# Power.net
KiCad netlist of a schematic drawn in Altium Designer
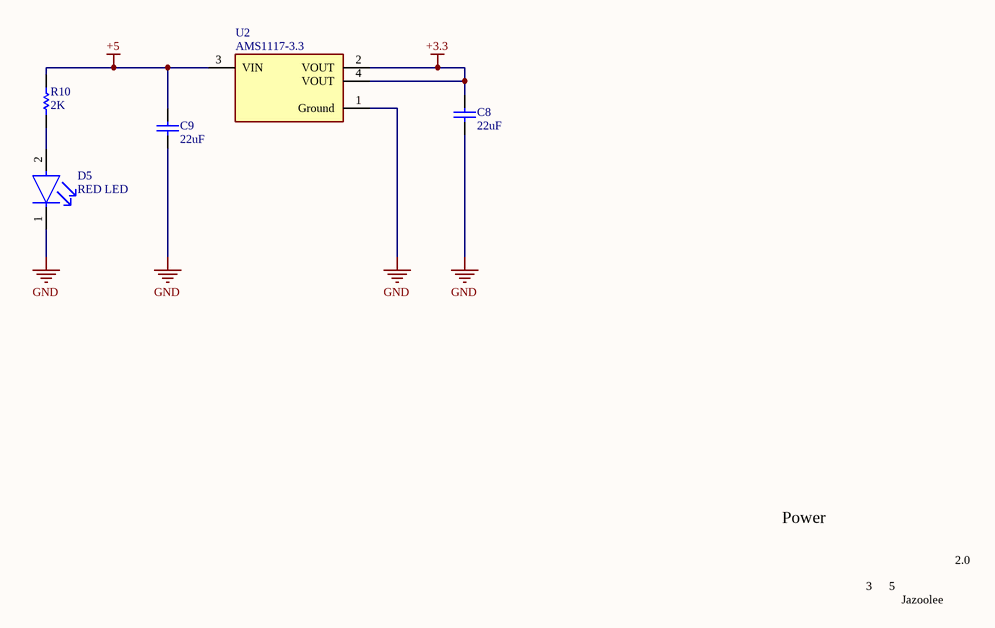
[diagram p0: Power.SchDoc]

(export (version "E")
  (design (tool "Eeschema 10.0.6"))
  (components
    (comp (ref "C8")
      (value "22uF")
      (footprint "CAPC2014X150X70ML20")
      (description "22uF 10V 20% Tantalum 0805")
      (fields
        (field (name "PART NUMBER") "TACR226M010XTA")
        (field (name "MANUFACTURER") "AVX Interconnect / Elco")
      )
      (libsource (lib "Altium Content Vault") (part "CAP"))
    )
    (comp (ref "C9")
      (value "22uF")
      (footprint "CAPC2014X150X70ML20")
      (description "22uF 10V 20% Tantalum 0805")
      (fields
        (field (name "PART NUMBER") "TACR226M010XTA")
        (field (name "MANUFACTURER") "AVX Interconnect / Elco")
      )
      (libsource (lib "Altium Content Vault") (part "CAP"))
    )
    (comp (ref "D5")
      (value "HSMS-C150")
      (footprint "FP-HSMS-C150-MFG")
      (description "LED RED")
      (fields (field (name "COLOR") "RED LED"))
      (libsource (lib "Altium Content Vault") (part "8706943c75ba83719d021d2fdc84c58"))
    )
    (comp (ref "R10")
      (value "2K")
      (footprint "RESC2013X60X35LL10T20")
      (fields (field (name "PART NUMBER") "RT0805FRE072KL") (field (name "MANUFACTURER") "Yageo"))
      (libsource (lib "Altium Content Vault") (part "RES"))
    )
    (comp (ref "U2")
      (value "AMS1117-3.3")
      (footprint "FP-AMS1117-IPC_A")
      (description "LDO Voltage Regulators 1A, 3.3V")
      (fields
        (field (name "OCTOPART") "https://octopart.com/ams1117-3.3-advanced+monolithic+systems-25899300")
        (field (name "MANUFACTURER") "Advanced Monolithic Systems")
      )
      (libsource (lib "Altium Content Vault") (part "8bdbb5f8e77002000e30dd2845d0354"))
    )
  )
  (nets
    (net (code "1") (name "+3.3") (class "Default")
      (node (ref "C8") (pin "2") (pinfunction "2_2") (pintype "passive"))
      (node (ref "U2") (pin "2") (pinfunction "VOUT_2") (pintype "passive"))
      (node (ref "U2") (pin "4") (pinfunction "VOUT_4") (pintype "passive"))
    )
    (net (code "2") (name "+5") (class "Default")
      (node (ref "C9") (pin "2") (pinfunction "2_2") (pintype "passive"))
      (node (ref "R10") (pin "2") (pinfunction "2_2") (pintype "passive"))
      (node (ref "U2") (pin "3") (pinfunction "VIN_3") (pintype "power_in"))
    )
    (net (code "3") (name "GND") (class "Default")
      (node (ref "C8") (pin "1") (pinfunction "1_1") (pintype "passive"))
      (node (ref "C9") (pin "1") (pinfunction "1_1") (pintype "passive"))
      (node (ref "D5") (pin "1") (pinfunction "C_1") (pintype "passive"))
      (node (ref "U2") (pin "1") (pinfunction "Ground_1") (pintype "power_in"))
    )
    (net (code "4") (name "Net-(D5-A)") (class "Default")
      (node (ref "D5") (pin "2") (pinfunction "A_2") (pintype "passive"))
      (node (ref "R10") (pin "1") (pinfunction "1_1") (pintype "passive"))
    )
  )
)
